# temperature_m.net
KiCad netlist of a schematic drawn in Altium Designer
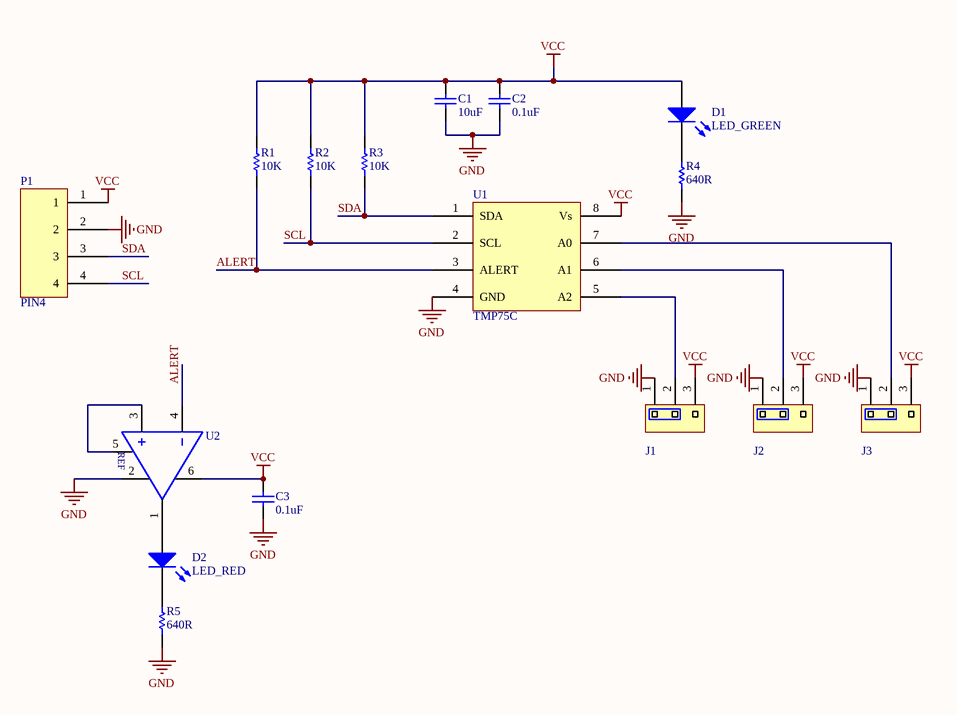
[diagram p0: temperature_m.SchDoc]

(export (version "E")
  (design (tool "Eeschema 10.0.6"))
  (components
    (comp (ref "C1")
      (value "10uF")
      (footprint "CAP0805")
      (fields (field (name "Comment") "CAP"))
      (libsource (lib "Warrison") (part "CAP1"))
    )
    (comp (ref "C2")
      (value "0.1uF")
      (footprint "CAP0805")
      (fields (field (name "Comment") "CAP"))
      (libsource (lib "Warrison") (part "CAP1"))
    )
    (comp (ref "C3")
      (value "0.1uF")
      (footprint "CAP0805")
      (fields (field (name "Comment") "CAP"))
      (libsource (lib "Warrison") (part "CAP1"))
    )
    (comp (ref "D1") (value "LED_GREEN") (footprint "LED0805") (libsource (lib "Warrison") (part "LED")))
    (comp (ref "D2") (value "LED_RED") (footprint "LED0805") (libsource (lib "Warrison") (part "LED")))
    (comp (ref "J1")
      (value "J Jumper_COM_L")
      (footprint "PIN3")
      (libsource (lib "Warrison") (part "J Jumper_COM_L"))
    )
    (comp (ref "J2")
      (value "J Jumper_COM_L")
      (footprint "PIN3")
      (libsource (lib "Warrison") (part "J Jumper_COM_L"))
    )
    (comp (ref "J3")
      (value "J Jumper_COM_L")
      (footprint "PIN3")
      (libsource (lib "Warrison") (part "J Jumper_COM_L"))
    )
    (comp (ref "P1") (value "PIN4") (footprint "PIN4") (libsource (lib "Warrison") (part "PIN4")))
    (comp (ref "R1")
      (value "10K")
      (footprint "RES0805")
      (fields (field (name "Comment") "RES"))
      (libsource (lib "Warrison") (part "RES1"))
    )
    (comp (ref "R2")
      (value "10K")
      (footprint "RES0805")
      (fields (field (name "Comment") "RES"))
      (libsource (lib "Warrison") (part "RES1"))
    )
    (comp (ref "R3")
      (value "10K")
      (footprint "RES0805")
      (fields (field (name "Comment") "RES"))
      (libsource (lib "Warrison") (part "RES1"))
    )
    (comp (ref "R4")
      (value "640R")
      (footprint "RES0805")
      (fields (field (name "Comment") "RES"))
      (libsource (lib "Warrison") (part "RES1"))
    )
    (comp (ref "R5")
      (value "640R")
      (footprint "RES0805")
      (fields (field (name "Comment") "RES"))
      (libsource (lib "Warrison") (part "RES1"))
    )
    (comp (ref "U1")
      (value "TMP75C")
      (footprint "SOIC8")
      (description "Digital temperature sensor chip, The lowest power supply 1.8v, Operation temp: -55 to 125")
      (libsource (lib "Warrison_Chips") (part "TMP75C"))
    )
    (comp (ref "U2")
      (value "CMP  SOT23")
      (footprint "SOT23-6")
      (description "Comparator with Voltage Reference")
      (libsource (lib "Warrison") (part "CMP SOT23"))
    )
  )
  (nets
    (net (code "1") (name "/ALERT") (class "Default")
      (node (ref "R1") (pin "1") (pinfunction "1_1") (pintype "passive"))
      (node (ref "U1") (pin "3") (pinfunction "ALERT_3") (pintype "passive"))
      (node (ref "U2") (pin "4") (pinfunction "IN-_4") (pintype "passive"))
    )
    (net (code "2") (name "/SCL") (class "Default")
      (node (ref "P1") (pin "4") (pinfunction "4_4") (pintype "passive"))
      (node (ref "R2") (pin "1") (pinfunction "1_1") (pintype "passive"))
      (node (ref "U1") (pin "2") (pinfunction "SCL_2") (pintype "passive"))
    )
    (net (code "3") (name "/SDA") (class "Default")
      (node (ref "P1") (pin "3") (pinfunction "3_3") (pintype "passive"))
      (node (ref "R3") (pin "1") (pinfunction "1_1") (pintype "passive"))
      (node (ref "U1") (pin "1") (pinfunction "SDA_1") (pintype "passive"))
    )
    (net (code "4") (name "GND") (class "Default")
      (node (ref "C1") (pin "1") (pinfunction "1_1") (pintype "passive"))
      (node (ref "C2") (pin "1") (pinfunction "1_1") (pintype "passive"))
      (node (ref "C3") (pin "1") (pinfunction "1_1") (pintype "passive"))
      (node (ref "J1") (pin "1") (pinfunction "1_1") (pintype "passive"))
      (node (ref "J2") (pin "1") (pinfunction "1_1") (pintype "passive"))
      (node (ref "J3") (pin "1") (pinfunction "1_1") (pintype "passive"))
      (node (ref "P1") (pin "2") (pinfunction "2_2") (pintype "passive"))
      (node (ref "R4") (pin "1") (pinfunction "1_1") (pintype "passive"))
      (node (ref "R5") (pin "1") (pinfunction "1_1") (pintype "passive"))
      (node (ref "U1") (pin "4") (pinfunction "GND_4") (pintype "passive"))
      (node (ref "U2") (pin "2") (pinfunction "V-_2") (pintype "passive"))
    )
    (net (code "5") (name "Net-(D1-K)") (class "Default")
      (node (ref "D1") (pin "2") (pinfunction "K_2") (pintype "passive"))
      (node (ref "R4") (pin "2") (pinfunction "2_2") (pintype "passive"))
    )
    (net (code "6") (name "Net-(D2-A)") (class "Default")
      (node (ref "D2") (pin "1") (pinfunction "A_1") (pintype "passive"))
      (node (ref "U2") (pin "1") (pinfunction "Out_1") (pintype "passive"))
    )
    (net (code "7") (name "Net-(D2-K)") (class "Default")
      (node (ref "D2") (pin "2") (pinfunction "K_2") (pintype "passive"))
      (node (ref "R5") (pin "2") (pinfunction "2_2") (pintype "passive"))
    )
    (net (code "8") (name "Net-(U1-A0)") (class "Default")
      (node (ref "J3") (pin "2") (pinfunction "2_2") (pintype "passive"))
      (node (ref "U1") (pin "7") (pinfunction "A0_7") (pintype "passive"))
    )
    (net (code "9") (name "Net-(U1-A1)") (class "Default")
      (node (ref "J2") (pin "2") (pinfunction "2_2") (pintype "passive"))
      (node (ref "U1") (pin "6") (pinfunction "A1_6") (pintype "passive"))
    )
    (net (code "10") (name "Net-(U1-A2)") (class "Default")
      (node (ref "J1") (pin "2") (pinfunction "2_2") (pintype "passive"))
      (node (ref "U1") (pin "5") (pinfunction "A2_5") (pintype "passive"))
    )
    (net (code "11") (name "Net-(U2-IN+)") (class "Default")
      (node (ref "U2") (pin "3") (pinfunction "IN+_3") (pintype "passive"))
      (node (ref "U2") (pin "5") (pinfunction "Ref_5") (pintype "passive"))
    )
    (net (code "12") (name "VCC") (class "Default")
      (node (ref "C1") (pin "2") (pinfunction "2_2") (pintype "passive"))
      (node (ref "C2") (pin "2") (pinfunction "2_2") (pintype "passive"))
      (node (ref "C3") (pin "2") (pinfunction "2_2") (pintype "passive"))
      (node (ref "D1") (pin "1") (pinfunction "A_1") (pintype "passive"))
      (node (ref "J1") (pin "3") (pinfunction "3_3") (pintype "passive"))
      (node (ref "J2") (pin "3") (pinfunction "3_3") (pintype "passive"))
      (node (ref "J3") (pin "3") (pinfunction "3_3") (pintype "passive"))
      (node (ref "P1") (pin "1") (pinfunction "1_1") (pintype "passive"))
      (node (ref "R1") (pin "2") (pinfunction "2_2") (pintype "passive"))
      (node (ref "R2") (pin "2") (pinfunction "2_2") (pintype "passive"))
      (node (ref "R3") (pin "2") (pinfunction "2_2") (pintype "passive"))
      (node (ref "U1") (pin "8") (pinfunction "Vs_8") (pintype "passive"))
      (node (ref "U2") (pin "6") (pinfunction "V+_6") (pintype "passive"))
    )
  )
)
